# letter_p.net
KiCad netlist of a schematic drawn in EAGLE
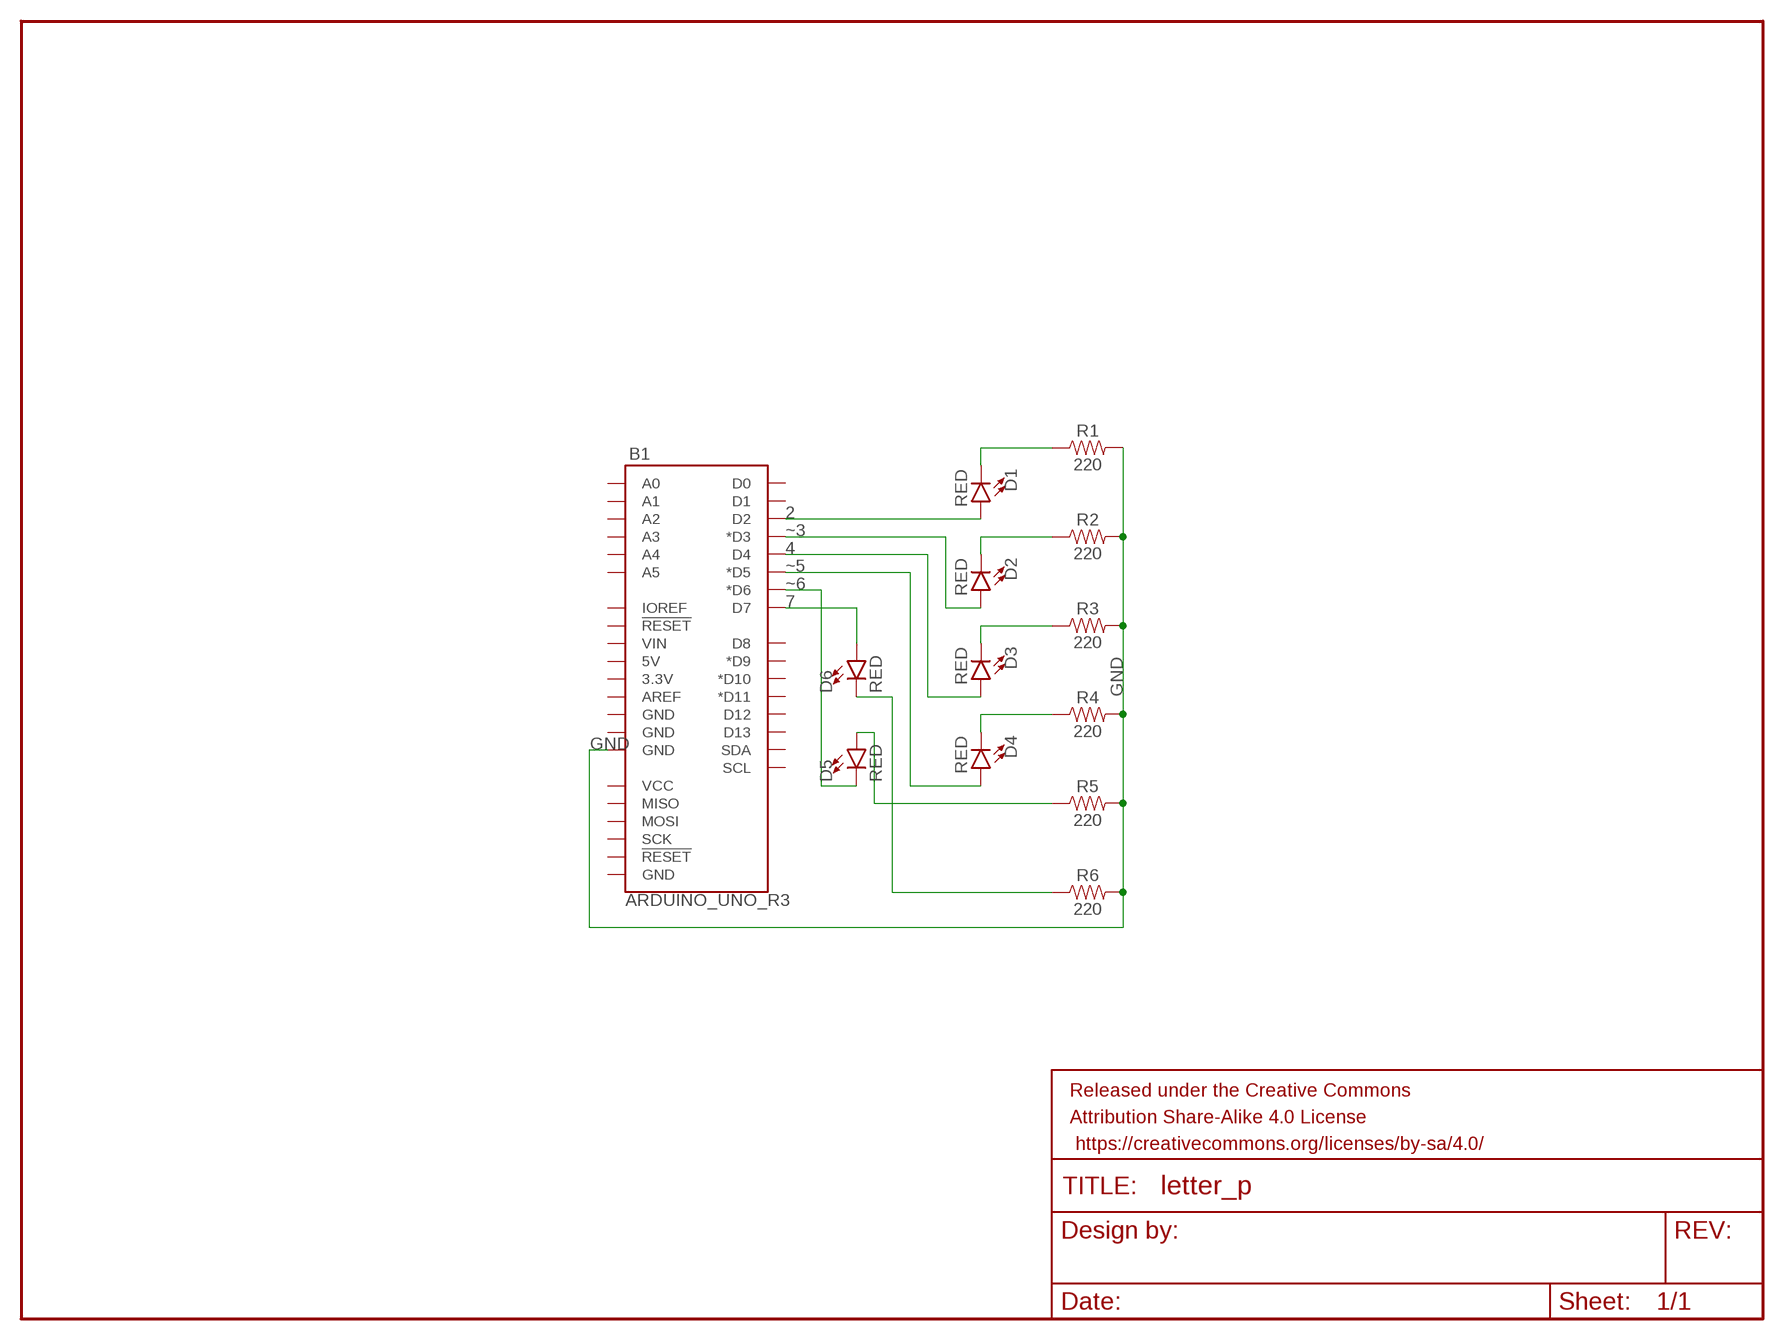
[diagram p0: schematic, sheet 1]

(export (version "E")
  (design (tool "Eeschema 10.0.6"))
  (components
    (comp (ref "B1")
      (value "ARDUINO_UNO_R3")
      (footprint "eagle-import:ARDUINO_R3")
      (libsource (lib "eagle-import") (part "ARDUINO_UNO_R3"))
    )
    (comp (ref "D1")
      (value "RED")
      (footprint "eagle-import:LED_5MM")
      (libsource (lib "eagle-import") (part "LED5MM"))
    )
    (comp (ref "D2")
      (value "RED")
      (footprint "eagle-import:LED_5MM")
      (libsource (lib "eagle-import") (part "LED5MM"))
    )
    (comp (ref "D3")
      (value "RED")
      (footprint "eagle-import:LED_5MM")
      (libsource (lib "eagle-import") (part "LED5MM"))
    )
    (comp (ref "D4")
      (value "RED")
      (footprint "eagle-import:LED_5MM")
      (libsource (lib "eagle-import") (part "LED5MM"))
    )
    (comp (ref "D5")
      (value "RED")
      (footprint "eagle-import:LED_5MM")
      (libsource (lib "eagle-import") (part "LED5MM"))
    )
    (comp (ref "D6")
      (value "RED")
      (footprint "eagle-import:LED_5MM")
      (libsource (lib "eagle-import") (part "LED5MM"))
    )
    (comp (ref "FRAME1")
      (value "FRAME-LETTER")
      (footprint "eagle-import:CREATIVE_COMMONS")
      (libsource (lib "eagle-import") (part "FRAME-LETTER"))
    )
    (comp (ref "R1")
      (value "220")
      (footprint "eagle-import:AXIAL-0.3")
      (libsource (lib "eagle-import") (part "1KOHM-HORIZ-1/4W-5%"))
    )
    (comp (ref "R2")
      (value "220")
      (footprint "eagle-import:AXIAL-0.3")
      (libsource (lib "eagle-import") (part "1KOHM-HORIZ-1/4W-5%"))
    )
    (comp (ref "R3")
      (value "220")
      (footprint "eagle-import:AXIAL-0.3")
      (libsource (lib "eagle-import") (part "1KOHM-HORIZ-1/4W-5%"))
    )
    (comp (ref "R4")
      (value "220")
      (footprint "eagle-import:AXIAL-0.3")
      (libsource (lib "eagle-import") (part "1KOHM-HORIZ-1/4W-5%"))
    )
    (comp (ref "R5")
      (value "220")
      (footprint "eagle-import:AXIAL-0.3")
      (libsource (lib "eagle-import") (part "1KOHM-HORIZ-1/4W-5%"))
    )
    (comp (ref "R6")
      (value "220")
      (footprint "eagle-import:AXIAL-0.3")
      (libsource (lib "eagle-import") (part "1KOHM-HORIZ-1/4W-5%"))
    )
  )
  (nets
    (net (code "1") (name "/2") (class "Default")
      (node (ref "B1") (pin "D2") (pinfunction "D2_D2") (pintype "bidirectional"))
      (node (ref "D1") (pin "A") (pinfunction "A_A") (pintype "passive"))
    )
    (net (code "2") (name "/4") (class "Default")
      (node (ref "B1") (pin "D4") (pinfunction "D4_D4") (pintype "bidirectional"))
      (node (ref "D3") (pin "A") (pinfunction "A_A") (pintype "passive"))
    )
    (net (code "3") (name "/7") (class "Default")
      (node (ref "B1") (pin "D7") (pinfunction "D7_D7") (pintype "bidirectional"))
      (node (ref "D6") (pin "A") (pinfunction "A_A") (pintype "passive"))
    )
    (net (code "4") (name "/GND") (class "Default")
      (node (ref "B1") (pin "GND@2") (pinfunction "GND_GND@2") (pintype "bidirectional"))
      (node (ref "R1") (pin "P$2") (pinfunction "2_P$2") (pintype "passive"))
      (node (ref "R2") (pin "P$2") (pinfunction "2_P$2") (pintype "passive"))
      (node (ref "R3") (pin "P$2") (pinfunction "2_P$2") (pintype "passive"))
      (node (ref "R4") (pin "P$2") (pinfunction "2_P$2") (pintype "passive"))
      (node (ref "R5") (pin "P$2") (pinfunction "2_P$2") (pintype "passive"))
      (node (ref "R6") (pin "P$2") (pinfunction "2_P$2") (pintype "passive"))
    )
    (net (code "5") (name "/~{3}") (class "Default")
      (node (ref "B1") (pin "D3") (pinfunction "*D3_D3") (pintype "bidirectional"))
      (node (ref "D2") (pin "A") (pinfunction "A_A") (pintype "passive"))
    )
    (net (code "6") (name "/~{5}") (class "Default")
      (node (ref "B1") (pin "D5") (pinfunction "*D5_D5") (pintype "bidirectional"))
      (node (ref "D4") (pin "A") (pinfunction "A_A") (pintype "passive"))
    )
    (net (code "7") (name "/~{6}") (class "Default")
      (node (ref "B1") (pin "D6") (pinfunction "*D6_D6") (pintype "bidirectional"))
      (node (ref "D5") (pin "K") (pinfunction "C_K") (pintype "passive"))
    )
    (net (code "8") (name "Net-(D1-C)") (class "Default")
      (node (ref "D1") (pin "K") (pinfunction "C_K") (pintype "passive"))
      (node (ref "R1") (pin "P$1") (pinfunction "1_P$1") (pintype "passive"))
    )
    (net (code "9") (name "Net-(D2-C)") (class "Default")
      (node (ref "D2") (pin "K") (pinfunction "C_K") (pintype "passive"))
      (node (ref "R2") (pin "P$1") (pinfunction "1_P$1") (pintype "passive"))
    )
    (net (code "10") (name "Net-(D3-C)") (class "Default")
      (node (ref "D3") (pin "K") (pinfunction "C_K") (pintype "passive"))
      (node (ref "R3") (pin "P$1") (pinfunction "1_P$1") (pintype "passive"))
    )
    (net (code "11") (name "Net-(D4-C)") (class "Default")
      (node (ref "D4") (pin "K") (pinfunction "C_K") (pintype "passive"))
      (node (ref "R4") (pin "P$1") (pinfunction "1_P$1") (pintype "passive"))
    )
    (net (code "12") (name "Net-(D6-C)") (class "Default")
      (node (ref "D6") (pin "K") (pinfunction "C_K") (pintype "passive"))
      (node (ref "R6") (pin "P$1") (pinfunction "1_P$1") (pintype "passive"))
    )
    (net (code "13") (name "Net-(R5-1)") (class "Default")
      (node (ref "D5") (pin "A") (pinfunction "A_A") (pintype "passive"))
      (node (ref "R5") (pin "P$1") (pinfunction "1_P$1") (pintype "passive"))
    )
    (net (code "14") (name "unconnected-(B1-*D9-PadD9)") (class "Default")
      (node (ref "B1") (pin "D9") (pinfunction "*D9_D9") (pintype "bidirectional"))
    )
    (net (code "15") (name "unconnected-(B1-*D10-PadD10)") (class "Default")
      (node (ref "B1") (pin "D10") (pinfunction "*D10_D10") (pintype "bidirectional"))
    )
    (net (code "16") (name "unconnected-(B1-*D11-PadD11)") (class "Default")
      (node (ref "B1") (pin "D11") (pinfunction "*D11_D11") (pintype "bidirectional"))
    )
    (net (code "17") (name "unconnected-(B1-GND-PadGND@1)") (class "Default")
      (node (ref "B1") (pin "GND@1") (pinfunction "GND_GND@1") (pintype "bidirectional"))
    )
    (net (code "18") (name "unconnected-(B1-GND-PadGND@3)") (class "Default")
      (node (ref "B1") (pin "GND@3") (pinfunction "GND_GND@3") (pintype "bidirectional"))
    )
    (net (code "19") (name "unconnected-(B1-GND-PadGND@4)") (class "Default")
      (node (ref "B1") (pin "GND@4") (pinfunction "GND_GND@4") (pintype "bidirectional"))
    )
    (net (code "20") (name "unconnected-(B1-Pad3.3V)") (class "Default")
      (node (ref "B1") (pin "3.3V") (pinfunction "3.3V_3.3V") (pintype "bidirectional"))
    )
    (net (code "21") (name "unconnected-(B1-Pad5V)") (class "Default")
      (node (ref "B1") (pin "5V") (pinfunction "5V_5V") (pintype "bidirectional"))
    )
    (net (code "22") (name "unconnected-(B1-PadA0)") (class "Default")
      (node (ref "B1") (pin "A0") (pinfunction "A0_A0") (pintype "bidirectional"))
    )
    (net (code "23") (name "unconnected-(B1-PadA1)") (class "Default")
      (node (ref "B1") (pin "A1") (pinfunction "A1_A1") (pintype "bidirectional"))
    )
    (net (code "24") (name "unconnected-(B1-PadA2)") (class "Default")
      (node (ref "B1") (pin "A2") (pinfunction "A2_A2") (pintype "bidirectional"))
    )
    (net (code "25") (name "unconnected-(B1-PadA3)") (class "Default")
      (node (ref "B1") (pin "A3") (pinfunction "A3_A3") (pintype "bidirectional"))
    )
    (net (code "26") (name "unconnected-(B1-PadA4)") (class "Default")
      (node (ref "B1") (pin "A4") (pinfunction "A4_A4") (pintype "bidirectional"))
    )
    (net (code "27") (name "unconnected-(B1-PadA5)") (class "Default")
      (node (ref "B1") (pin "A5") (pinfunction "A5_A5") (pintype "bidirectional"))
    )
    (net (code "28") (name "unconnected-(B1-PadAREF)") (class "Default")
      (node (ref "B1") (pin "AREF") (pinfunction "AREF_AREF") (pintype "bidirectional"))
    )
    (net (code "29") (name "unconnected-(B1-PadD0)") (class "Default")
      (node (ref "B1") (pin "D0") (pinfunction "D0_D0") (pintype "bidirectional"))
    )
    (net (code "30") (name "unconnected-(B1-PadD1)") (class "Default")
      (node (ref "B1") (pin "D1") (pinfunction "D1_D1") (pintype "bidirectional"))
    )
    (net (code "31") (name "unconnected-(B1-PadD8)") (class "Default")
      (node (ref "B1") (pin "D8") (pinfunction "D8_D8") (pintype "bidirectional"))
    )
    (net (code "32") (name "unconnected-(B1-PadD12)") (class "Default")
      (node (ref "B1") (pin "D12") (pinfunction "D12_D12") (pintype "bidirectional"))
    )
    (net (code "33") (name "unconnected-(B1-PadD13)") (class "Default")
      (node (ref "B1") (pin "D13") (pinfunction "D13_D13") (pintype "bidirectional"))
    )
    (net (code "34") (name "unconnected-(B1-PadIOREF)") (class "Default")
      (node (ref "B1") (pin "IOREF") (pinfunction "IOREF_IOREF") (pintype "bidirectional"))
    )
    (net (code "35") (name "unconnected-(B1-PadMISO)") (class "Default")
      (node (ref "B1") (pin "MISO") (pinfunction "MISO_MISO") (pintype "bidirectional"))
    )
    (net (code "36") (name "unconnected-(B1-PadMOSI)") (class "Default")
      (node (ref "B1") (pin "MOSI") (pinfunction "MOSI_MOSI") (pintype "bidirectional"))
    )
    (net (code "37") (name "unconnected-(B1-PadSCK)") (class "Default")
      (node (ref "B1") (pin "SCK") (pinfunction "SCK_SCK") (pintype "bidirectional"))
    )
    (net (code "38") (name "unconnected-(B1-PadSCL)") (class "Default")
      (node (ref "B1") (pin "SCL") (pinfunction "SCL_SCL") (pintype "bidirectional"))
    )
    (net (code "39") (name "unconnected-(B1-PadSDA)") (class "Default")
      (node (ref "B1") (pin "SDA") (pinfunction "SDA_SDA") (pintype "bidirectional"))
    )
    (net (code "40") (name "unconnected-(B1-PadVCC)") (class "Default")
      (node (ref "B1") (pin "VCC") (pinfunction "VCC_VCC") (pintype "bidirectional"))
    )
    (net (code "41") (name "unconnected-(B1-PadVIN)") (class "Default")
      (node (ref "B1") (pin "VIN") (pinfunction "VIN_VIN") (pintype "bidirectional"))
    )
    (net (code "42") (name "unconnected-(B1-~{RESET}-PadRESET@1)") (class "Default")
      (node (ref "B1") (pin "RESET@1") (pinfunction "~{RESET}_RESET@1") (pintype "bidirectional"))
    )
    (net (code "43") (name "unconnected-(B1-~{RESET}-PadRESET@2)") (class "Default")
      (node (ref "B1") (pin "RESET@2") (pinfunction "~{RESET}_RESET@2") (pintype "bidirectional"))
    )
  )
)
